# rev01.net
KiCad netlist of a schematic drawn in EAGLE
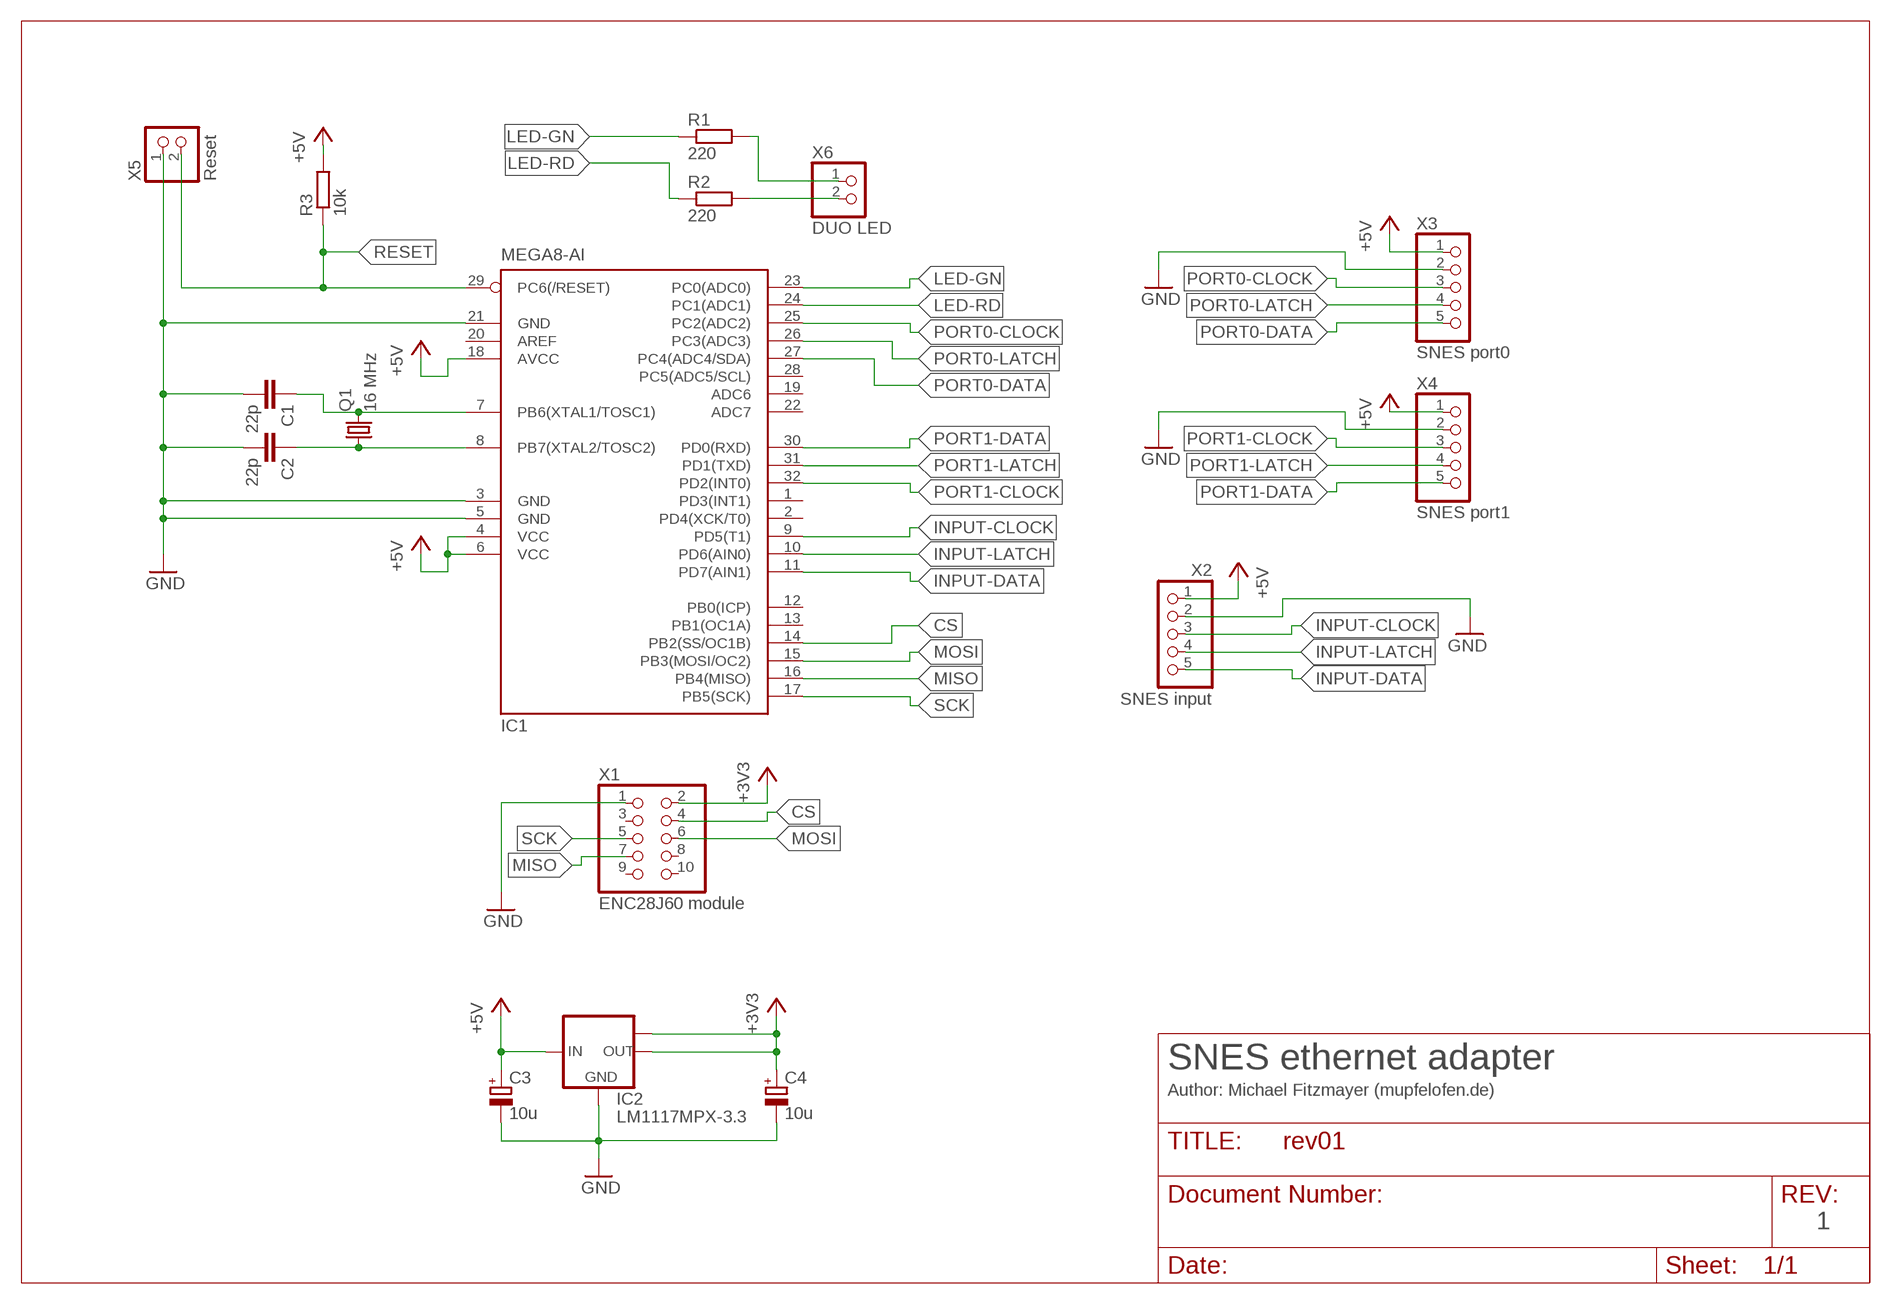
[diagram p0: schematic, sheet 1]

(export (version "E")
  (design (tool "Eeschema 10.0.6"))
  (components
    (comp (ref "C1")
      (value "22p")
      (footprint "eagle-import:C1206")
      (libsource (lib "eagle-import") (part "C-EUC1206"))
    )
    (comp (ref "C2")
      (value "22p")
      (footprint "eagle-import:C1206")
      (libsource (lib "eagle-import") (part "C-EUC1206"))
    )
    (comp (ref "C3")
      (value "10u")
      (footprint "eagle-import:C_6032-28R")
      (libsource (lib "eagle-import") (part "CPOL-EUC/6032-28R"))
    )
    (comp (ref "C4")
      (value "10u")
      (footprint "eagle-import:C_6032-28R")
      (libsource (lib "eagle-import") (part "CPOL-EUC/6032-28R"))
    )
    (comp (ref "IC1")
      (value "MEGA8-AI")
      (footprint "eagle-import:TQFP32-08")
      (fields (field (name "MPN") "ATMEGA8-16AU"))
      (libsource (lib "eagle-import") (part "MEGA8-AI"))
    )
    (comp (ref "IC2")
      (value "LM1117MPX-3.3")
      (footprint "eagle-import:SOT223")
      (libsource (lib "eagle-import") (part "LM1117MPX-3.3"))
    )
    (comp (ref "Q1")
      (value "16 MHz")
      (footprint "eagle-import:SM49")
      (libsource (lib "eagle-import") (part "CRYSTALSM49"))
    )
    (comp (ref "R1")
      (value "220")
      (footprint "eagle-import:R1206")
      (libsource (lib "eagle-import") (part "R-EU_R1206"))
    )
    (comp (ref "R2")
      (value "220")
      (footprint "eagle-import:R1206")
      (libsource (lib "eagle-import") (part "R-EU_R1206"))
    )
    (comp (ref "R3")
      (value "10k")
      (footprint "eagle-import:R1206")
      (libsource (lib "eagle-import") (part "R-EU_R1206"))
    )
    (comp (ref "X1")
      (value "ENC28J60 module")
      (footprint "eagle-import:2X05SMD")
      (libsource (lib "eagle-import") (part "PINHD-2X5_2.54-SMD"))
    )
    (comp (ref "X2")
      (value "SNES input")
      (footprint "eagle-import:1X05SMD")
      (libsource (lib "eagle-import") (part "PINHD-1X5_2.54-SMD"))
    )
    (comp (ref "X3")
      (value "SNES port0")
      (footprint "eagle-import:1X05SMD")
      (libsource (lib "eagle-import") (part "PINHD-1X5_2.54-SMD"))
    )
    (comp (ref "X4")
      (value "SNES port1")
      (footprint "eagle-import:1X05SMD")
      (libsource (lib "eagle-import") (part "PINHD-1X5_2.54-SMD"))
    )
    (comp (ref "X5")
      (value "Reset")
      (footprint "eagle-import:1X02SMD")
      (libsource (lib "eagle-import") (part "PINHD-1X2_2.54-SMD"))
    )
    (comp (ref "X6")
      (value "DUO LED")
      (footprint "eagle-import:1X02SMD")
      (libsource (lib "eagle-import") (part "PINHD-1X2_2.54-SMD"))
    )
  )
  (nets
    (net (code "1") (name "+3V3") (class "Default")
      (node (ref "C4") (pin "+") (pinfunction "+_+") (pintype "passive"))
      (node (ref "IC2") (pin "2") (pinfunction "OUT_2") (pintype "passive"))
      (node (ref "IC2") (pin "TAB") (pinfunction "OUT1_TAB") (pintype "passive"))
      (node (ref "X1") (pin "2") (pinfunction "2_2") (pintype "passive"))
    )
    (net (code "2") (name "+5V") (class "Default")
      (node (ref "C3") (pin "+") (pinfunction "+_+") (pintype "passive"))
      (node (ref "IC1") (pin "18") (pinfunction "AVCC_18") (pintype "power_in"))
      (node (ref "IC1") (pin "4") (pinfunction "VCC_4") (pintype "power_in"))
      (node (ref "IC1") (pin "6") (pinfunction "VCC_6") (pintype "power_in"))
      (node (ref "IC2") (pin "3") (pinfunction "IN_3") (pintype "input"))
      (node (ref "R3") (pin "2") (pinfunction "2_2") (pintype "passive"))
      (node (ref "X2") (pin "1") (pinfunction "1_1") (pintype "passive"))
      (node (ref "X3") (pin "1") (pinfunction "1_1") (pintype "passive"))
      (node (ref "X4") (pin "1") (pinfunction "1_1") (pintype "passive"))
    )
    (net (code "3") (name "CS") (class "Default")
      (node (ref "IC1") (pin "14") (pinfunction "PB2(SS/OC1B)_14") (pintype "bidirectional"))
      (node (ref "X1") (pin "4") (pinfunction "4_4") (pintype "passive"))
    )
    (net (code "4") (name "GND") (class "Default")
      (node (ref "C1") (pin "2") (pinfunction "2_2") (pintype "passive"))
      (node (ref "C2") (pin "2") (pinfunction "2_2") (pintype "passive"))
      (node (ref "C3") (pin "-") (pinfunction "-_-") (pintype "passive"))
      (node (ref "C4") (pin "-") (pinfunction "-_-") (pintype "passive"))
      (node (ref "IC1") (pin "21") (pinfunction "GND_21") (pintype "power_in"))
      (node (ref "IC1") (pin "3") (pinfunction "GND_3") (pintype "power_in"))
      (node (ref "IC1") (pin "5") (pinfunction "GND_5") (pintype "power_in"))
      (node (ref "IC2") (pin "1") (pinfunction "GND_1") (pintype "input"))
      (node (ref "X1") (pin "1") (pinfunction "1_1") (pintype "passive"))
      (node (ref "X2") (pin "2") (pinfunction "2_2") (pintype "passive"))
      (node (ref "X3") (pin "2") (pinfunction "2_2") (pintype "passive"))
      (node (ref "X4") (pin "2") (pinfunction "2_2") (pintype "passive"))
      (node (ref "X5") (pin "1") (pinfunction "1_1") (pintype "passive"))
    )
    (net (code "5") (name "INPUT-CLOCK") (class "Default")
      (node (ref "IC1") (pin "9") (pinfunction "PD5(T1)_9") (pintype "bidirectional"))
      (node (ref "X2") (pin "3") (pinfunction "3_3") (pintype "passive"))
    )
    (net (code "6") (name "INPUT-DATA") (class "Default")
      (node (ref "IC1") (pin "11") (pinfunction "PD7(AIN1)_11") (pintype "bidirectional"))
      (node (ref "X2") (pin "5") (pinfunction "5_5") (pintype "passive"))
    )
    (net (code "7") (name "INPUT-LATCH") (class "Default")
      (node (ref "IC1") (pin "10") (pinfunction "PD6(AIN0)_10") (pintype "bidirectional"))
      (node (ref "X2") (pin "4") (pinfunction "4_4") (pintype "passive"))
    )
    (net (code "8") (name "LED-GN") (class "Default")
      (node (ref "IC1") (pin "23") (pinfunction "PC0(ADC0)_23") (pintype "bidirectional"))
      (node (ref "R1") (pin "1") (pinfunction "1_1") (pintype "passive"))
    )
    (net (code "9") (name "LED-RD") (class "Default")
      (node (ref "IC1") (pin "24") (pinfunction "PC1(ADC1)_24") (pintype "bidirectional"))
      (node (ref "R2") (pin "1") (pinfunction "1_1") (pintype "passive"))
    )
    (net (code "10") (name "MISO") (class "Default")
      (node (ref "IC1") (pin "16") (pinfunction "PB4(MISO)_16") (pintype "bidirectional"))
      (node (ref "X1") (pin "7") (pinfunction "7_7") (pintype "passive"))
    )
    (net (code "11") (name "MOSI") (class "Default")
      (node (ref "IC1") (pin "15") (pinfunction "PB3(MOSI/OC2)_15") (pintype "bidirectional"))
      (node (ref "X1") (pin "6") (pinfunction "6_6") (pintype "passive"))
    )
    (net (code "12") (name "Net-(IC1-PB6(XTAL1{slash}TOSC1))") (class "Default")
      (node (ref "C1") (pin "1") (pinfunction "1_1") (pintype "passive"))
      (node (ref "IC1") (pin "7") (pinfunction "PB6(XTAL1/TOSC1)_7") (pintype "bidirectional"))
      (node (ref "Q1") (pin "2") (pinfunction "2_2") (pintype "passive"))
    )
    (net (code "13") (name "Net-(IC1-PB7(XTAL2{slash}TOSC2))") (class "Default")
      (node (ref "C2") (pin "1") (pinfunction "1_1") (pintype "passive"))
      (node (ref "IC1") (pin "8") (pinfunction "PB7(XTAL2/TOSC2)_8") (pintype "bidirectional"))
      (node (ref "Q1") (pin "1") (pinfunction "1_1") (pintype "passive"))
    )
    (net (code "14") (name "Net-(R1-Pad2)") (class "Default")
      (node (ref "R1") (pin "2") (pinfunction "2_2") (pintype "passive"))
      (node (ref "X6") (pin "1") (pinfunction "1_1") (pintype "passive"))
    )
    (net (code "15") (name "Net-(R2-Pad2)") (class "Default")
      (node (ref "R2") (pin "2") (pinfunction "2_2") (pintype "passive"))
      (node (ref "X6") (pin "2") (pinfunction "2_2") (pintype "passive"))
    )
    (net (code "16") (name "PORT0-CLOCK") (class "Default")
      (node (ref "IC1") (pin "25") (pinfunction "PC2(ADC2)_25") (pintype "bidirectional"))
      (node (ref "X3") (pin "3") (pinfunction "3_3") (pintype "passive"))
    )
    (net (code "17") (name "PORT0-DATA") (class "Default")
      (node (ref "IC1") (pin "27") (pinfunction "PC4(ADC4/SDA)_27") (pintype "bidirectional"))
      (node (ref "X3") (pin "5") (pinfunction "5_5") (pintype "passive"))
    )
    (net (code "18") (name "PORT0-LATCH") (class "Default")
      (node (ref "IC1") (pin "26") (pinfunction "PC3(ADC3)_26") (pintype "bidirectional"))
      (node (ref "X3") (pin "4") (pinfunction "4_4") (pintype "passive"))
    )
    (net (code "19") (name "PORT1-CLOCK") (class "Default")
      (node (ref "IC1") (pin "32") (pinfunction "PD2(INT0)_32") (pintype "bidirectional"))
      (node (ref "X4") (pin "3") (pinfunction "3_3") (pintype "passive"))
    )
    (net (code "20") (name "PORT1-DATA") (class "Default")
      (node (ref "IC1") (pin "30") (pinfunction "PD0(RXD)_30") (pintype "bidirectional"))
      (node (ref "X4") (pin "5") (pinfunction "5_5") (pintype "passive"))
    )
    (net (code "21") (name "PORT1-LATCH") (class "Default")
      (node (ref "IC1") (pin "31") (pinfunction "PD1(TXD)_31") (pintype "bidirectional"))
      (node (ref "X4") (pin "4") (pinfunction "4_4") (pintype "passive"))
    )
    (net (code "22") (name "RESET") (class "Default")
      (node (ref "IC1") (pin "29") (pinfunction "PC6(/RESET)_29") (pintype "bidirectional"))
      (node (ref "R3") (pin "1") (pinfunction "1_1") (pintype "passive"))
      (node (ref "X5") (pin "2") (pinfunction "2_2") (pintype "passive"))
    )
    (net (code "23") (name "SCK") (class "Default")
      (node (ref "IC1") (pin "17") (pinfunction "PB5(SCK)_17") (pintype "bidirectional"))
      (node (ref "X1") (pin "5") (pinfunction "5_5") (pintype "passive"))
    )
    (net (code "24") (name "unconnected-(IC1-ADC6-Pad19)") (class "Default")
      (node (ref "IC1") (pin "19") (pinfunction "ADC6_19") (pintype "bidirectional"))
    )
    (net (code "25") (name "unconnected-(IC1-ADC7-Pad22)") (class "Default")
      (node (ref "IC1") (pin "22") (pinfunction "ADC7_22") (pintype "bidirectional"))
    )
    (net (code "26") (name "unconnected-(IC1-AREF-Pad20)") (class "Default")
      (node (ref "IC1") (pin "20") (pinfunction "AREF_20") (pintype "passive"))
    )
    (net (code "27") (name "unconnected-(IC1-PB0(ICP)-Pad12)") (class "Default")
      (node (ref "IC1") (pin "12") (pinfunction "PB0(ICP)_12") (pintype "bidirectional"))
    )
    (net (code "28") (name "unconnected-(IC1-PB1(OC1A)-Pad13)") (class "Default")
      (node (ref "IC1") (pin "13") (pinfunction "PB1(OC1A)_13") (pintype "bidirectional"))
    )
    (net (code "29") (name "unconnected-(IC1-PC5(ADC5{slash}SCL)-Pad28)") (class "Default")
      (node (ref "IC1") (pin "28") (pinfunction "PC5(ADC5/SCL)_28") (pintype "bidirectional"))
    )
    (net (code "30") (name "unconnected-(IC1-PD3(INT1)-Pad1)") (class "Default")
      (node (ref "IC1") (pin "1") (pinfunction "PD3(INT1)_1") (pintype "bidirectional"))
    )
    (net (code "31") (name "unconnected-(IC1-PD4(XCK{slash}T0)-Pad2)") (class "Default")
      (node (ref "IC1") (pin "2") (pinfunction "PD4(XCK/T0)_2") (pintype "bidirectional"))
    )
    (net (code "32") (name "unconnected-(X1-Pad3)") (class "Default")
      (node (ref "X1") (pin "3") (pinfunction "3_3") (pintype "passive"))
    )
    (net (code "33") (name "unconnected-(X1-Pad8)") (class "Default")
      (node (ref "X1") (pin "8") (pinfunction "8_8") (pintype "passive"))
    )
    (net (code "34") (name "unconnected-(X1-Pad9)") (class "Default")
      (node (ref "X1") (pin "9") (pinfunction "9_9") (pintype "passive"))
    )
    (net (code "35") (name "unconnected-(X1-Pad10)") (class "Default")
      (node (ref "X1") (pin "10") (pinfunction "10_10") (pintype "passive"))
    )
  )
)
